# Blinky_Orlando.net
KiCad netlist of a schematic drawn in EAGLE
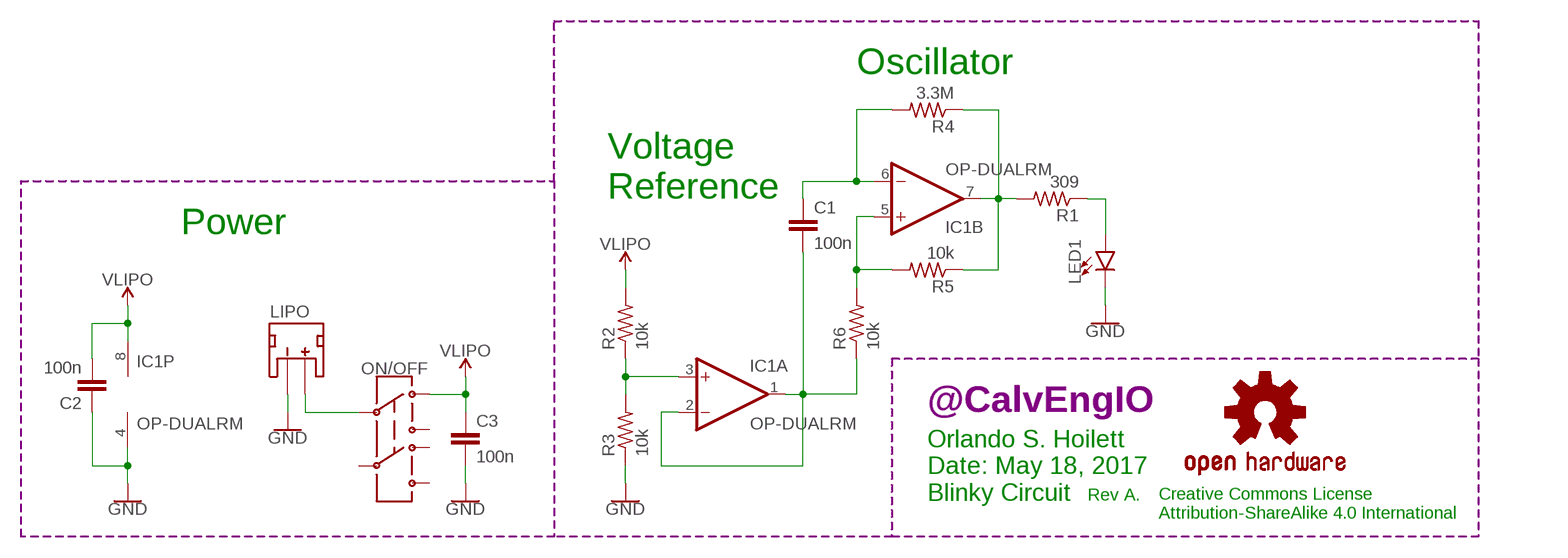
[diagram p0: schematic, sheet 1]

(export (version "E")
  (design (tool "Eeschema 10.0.6"))
  (components
    (comp (ref "C1")
      (value "100n")
      (footprint "eagle-import:C0402")
      (libsource (lib "eagle-import") (part "CAPACITOR0402"))
    )
    (comp (ref "C2")
      (value "100n")
      (footprint "eagle-import:C0402")
      (libsource (lib "eagle-import") (part "CAPACITOR0402"))
    )
    (comp (ref "C3")
      (value "100n")
      (footprint "eagle-import:C0402")
      (libsource (lib "eagle-import") (part "CAPACITOR0402"))
    )
    (comp (ref "IC1")
      (value "OP-DUALRM")
      (footprint "eagle-import:MSOP08")
      (fields (field (name "MF") "ALTERA CORPORATION") (field (name "MPN") "AD8607ARMZ-REEL"))
      (libsource (lib "eagle-import") (part "OP-DUALRM"))
    )
    (comp (ref "LED1")
      (value "LED0603")
      (footprint "eagle-import:LED-0603")
      (libsource (lib "eagle-import") (part "LED0603"))
    )
    (comp (ref "LIPO")
      (value "JST_2MM_MALE")
      (footprint "eagle-import:JST-2-SMD")
      (libsource (lib "eagle-import") (part "JST_2MM_MALE"))
    )
    (comp (ref "LOGO1")
      (value "OSHW-LOGOS")
      (footprint "eagle-import:OSHW-LOGO-S")
      (libsource (lib "eagle-import") (part "OSHW-LOGOS"))
    )
    (comp (ref "ON/OFF")
      (value "SWITCH.JS202011JCQN")
      (footprint "eagle-import:SWITCH.00")
      (libsource (lib "eagle-import") (part "SWITCH.JS202011JCQN"))
    )
    (comp (ref "R1")
      (value "309")
      (footprint "eagle-import:R0402")
      (libsource (lib "eagle-import") (part "RESISTOR0402"))
    )
    (comp (ref "R2")
      (value "10k")
      (footprint "eagle-import:R0402")
      (libsource (lib "eagle-import") (part "RESISTOR0402"))
    )
    (comp (ref "R3")
      (value "10k")
      (footprint "eagle-import:R0402")
      (libsource (lib "eagle-import") (part "RESISTOR0402"))
    )
    (comp (ref "R4")
      (value "3.3M")
      (footprint "eagle-import:R0402")
      (libsource (lib "eagle-import") (part "RESISTOR0402"))
    )
    (comp (ref "R5")
      (value "10k")
      (footprint "eagle-import:R0402")
      (libsource (lib "eagle-import") (part "RESISTOR0402"))
    )
    (comp (ref "R6")
      (value "10k")
      (footprint "eagle-import:R0402")
      (libsource (lib "eagle-import") (part "RESISTOR0402"))
    )
    (comp (ref "U$4")
      (value "CALVENGIO_HANDLEHANDLE.05")
      (footprint "eagle-import:CALVENGIO_HANDLE.05")
      (libsource (lib "eagle-import") (part "CALVENGIO_HANDLEHANDLE.05"))
    )
  )
  (nets
    (net (code "1") (name "GND") (class "Default")
      (node (ref "C2") (pin "1") (pinfunction "1_1") (pintype "passive"))
      (node (ref "C3") (pin "2") (pinfunction "2_2") (pintype "passive"))
      (node (ref "IC1") (pin "4") (pinfunction "V-_4") (pintype "power_in"))
      (node (ref "LED1") (pin "C") (pinfunction "C_C") (pintype "passive"))
      (node (ref "LIPO") (pin "1") (pinfunction "-_1") (pintype "bidirectional"))
      (node (ref "R3") (pin "1") (pinfunction "1_1") (pintype "passive"))
    )
    (net (code "2") (name "Net-(IC1A-+IN)") (class "Default")
      (node (ref "IC1") (pin "3") (pinfunction "+IN_3") (pintype "input"))
      (node (ref "R2") (pin "1") (pinfunction "1_1") (pintype "passive"))
      (node (ref "R3") (pin "2") (pinfunction "2_2") (pintype "passive"))
    )
    (net (code "3") (name "Net-(IC1A--IN)") (class "Default")
      (node (ref "C1") (pin "2") (pinfunction "2_2") (pintype "passive"))
      (node (ref "IC1") (pin "1") (pinfunction "OUT_1") (pintype "output"))
      (node (ref "IC1") (pin "2") (pinfunction "-IN_2") (pintype "input"))
      (node (ref "R6") (pin "1") (pinfunction "1_1") (pintype "passive"))
    )
    (net (code "4") (name "Net-(IC1B-+IN)") (class "Default")
      (node (ref "IC1") (pin "5") (pinfunction "+IN_5") (pintype "input"))
      (node (ref "R5") (pin "2") (pinfunction "2_2") (pintype "passive"))
      (node (ref "R6") (pin "2") (pinfunction "2_2") (pintype "passive"))
    )
    (net (code "5") (name "Net-(IC1B--IN)") (class "Default")
      (node (ref "C1") (pin "1") (pinfunction "1_1") (pintype "passive"))
      (node (ref "IC1") (pin "6") (pinfunction "-IN_6") (pintype "input"))
      (node (ref "R4") (pin "2") (pinfunction "2_2") (pintype "passive"))
    )
    (net (code "6") (name "Net-(IC1B-OUT)") (class "Default")
      (node (ref "IC1") (pin "7") (pinfunction "OUT_7") (pintype "output"))
      (node (ref "R1") (pin "2") (pinfunction "2_2") (pintype "passive"))
      (node (ref "R4") (pin "1") (pinfunction "1_1") (pintype "passive"))
      (node (ref "R5") (pin "1") (pinfunction "1_1") (pintype "passive"))
    )
    (net (code "7") (name "Net-(LED1-PadA)") (class "Default")
      (node (ref "LED1") (pin "A") (pinfunction "A_A") (pintype "passive"))
      (node (ref "R1") (pin "1") (pinfunction "1_1") (pintype "passive"))
    )
    (net (code "8") (name "Net-(LIPO-+)") (class "Default")
      (node (ref "LIPO") (pin "2") (pinfunction "+_2") (pintype "bidirectional"))
      (node (ref "ON/OFF") (pin "2") (pinfunction "2_2") (pintype "bidirectional"))
    )
    (net (code "9") (name "VLIPO") (class "Default")
      (node (ref "C2") (pin "2") (pinfunction "2_2") (pintype "passive"))
      (node (ref "C3") (pin "1") (pinfunction "1_1") (pintype "passive"))
      (node (ref "IC1") (pin "8") (pinfunction "V+_8") (pintype "power_in"))
      (node (ref "ON/OFF") (pin "1") (pinfunction "1_1") (pintype "bidirectional"))
      (node (ref "R2") (pin "2") (pinfunction "2_2") (pintype "passive"))
    )
    (net (code "10") (name "unconnected-(LIPO-PAD1-PadNC1)") (class "Default")
      (node (ref "LIPO") (pin "NC1") (pinfunction "PAD1_NC1") (pintype "bidirectional"))
    )
    (net (code "11") (name "unconnected-(LIPO-PAD2-PadNC2)") (class "Default")
      (node (ref "LIPO") (pin "NC2") (pinfunction "PAD2_NC2") (pintype "bidirectional"))
    )
    (net (code "12") (name "unconnected-(ON/OFF-Pad3)") (class "Default")
      (node (ref "ON/OFF") (pin "3") (pinfunction "3_3") (pintype "bidirectional"))
    )
    (net (code "13") (name "unconnected-(ON/OFF-Pad5)") (class "Default")
      (node (ref "ON/OFF") (pin "5") (pinfunction "5_5") (pintype "bidirectional"))
    )
    (net (code "14") (name "unconnected-(ON/OFF-Pad6)") (class "Default")
      (node (ref "ON/OFF") (pin "6") (pinfunction "6_6") (pintype "bidirectional"))
    )
    (net (code "15") (name "unconnected-(ON/OFF-Pad7)") (class "Default")
      (node (ref "ON/OFF") (pin "7") (pinfunction "7_7") (pintype "bidirectional"))
    )
  )
)
